# PreDAQ_Filter.net
KiCad netlist of a schematic drawn in Altium Designer
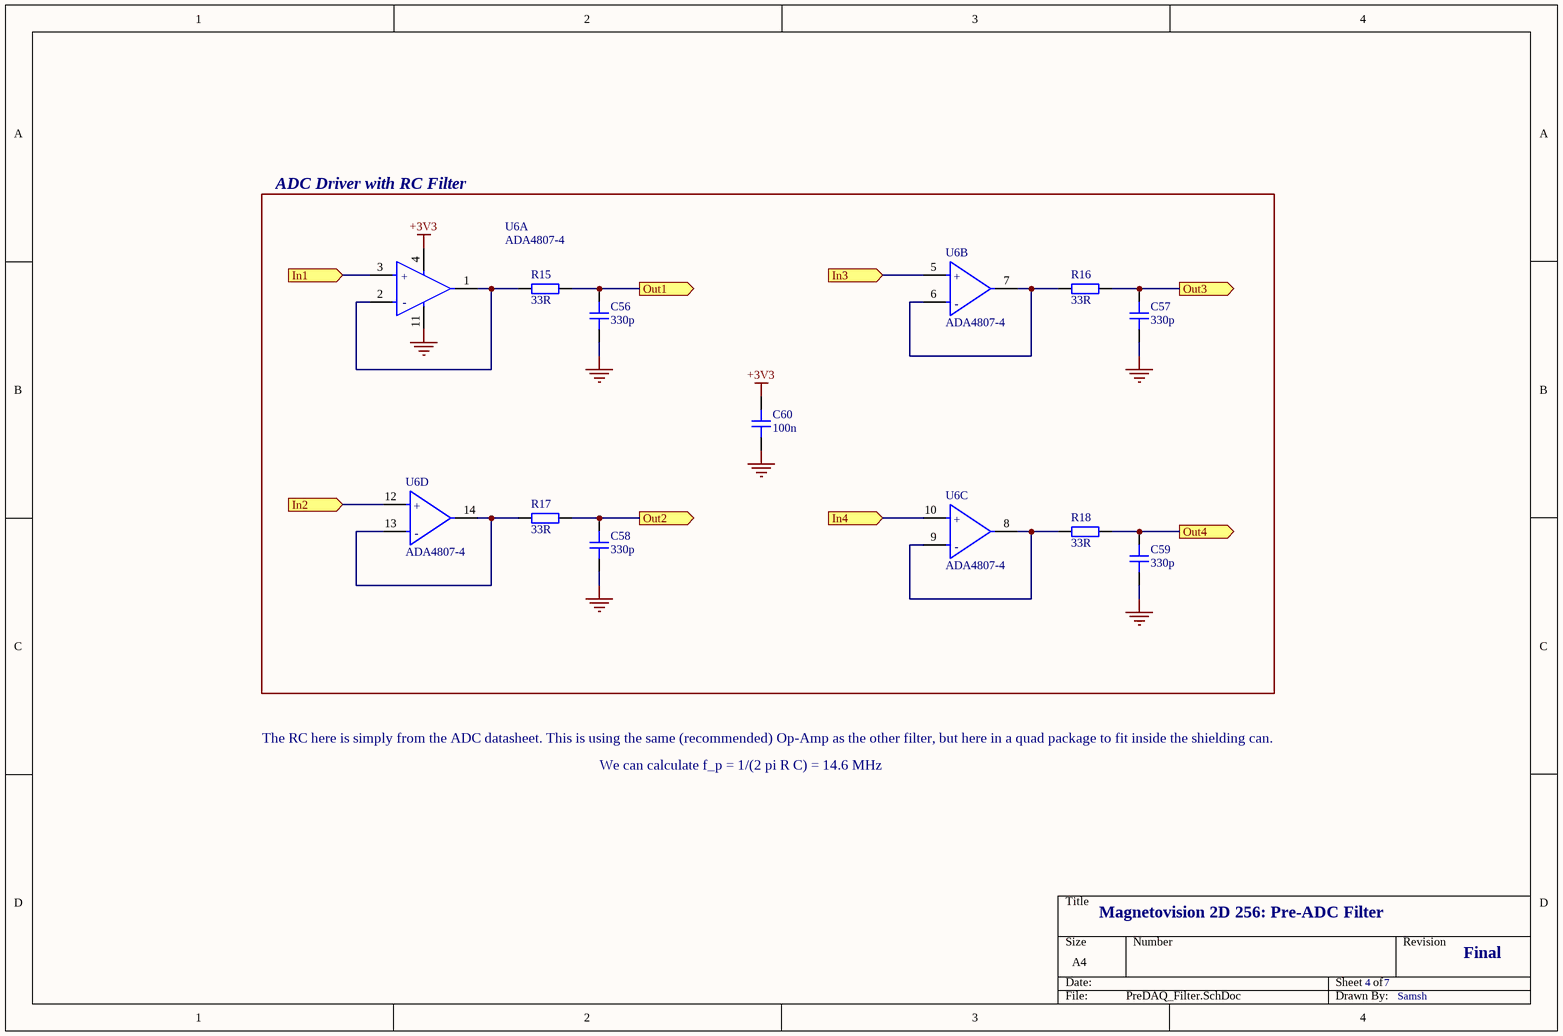
[diagram p0: PreDAQ_Filter.SchDoc]

(export (version "E")
  (design (tool "Eeschema 10.0.6"))
  (components
    (comp (ref "C56")
      (value "330p")
      (footprint "CAP_0603")
      (description "Capacitor SMD 0603")
      (fields (field (name "SOURCE") "Schematic-Lib-PhilsLab.SchLib"))
      (libsource (lib "Samsh Nanoelectronics") (part "CAP_EL_NP_5MM"))
    )
    (comp (ref "C57")
      (value "330p")
      (footprint "CAP_0603")
      (description "Capacitor SMD 0603")
      (fields (field (name "SOURCE") "Schematic-Lib-PhilsLab.SchLib"))
      (libsource (lib "Samsh Nanoelectronics") (part "CAP_EL_NP_5MM"))
    )
    (comp (ref "C58")
      (value "330p")
      (footprint "CAP_0603")
      (description "Capacitor SMD 0603")
      (fields (field (name "SOURCE") "Schematic-Lib-PhilsLab.SchLib"))
      (libsource (lib "Samsh Nanoelectronics") (part "CAP_EL_NP_5MM"))
    )
    (comp (ref "C59")
      (value "330p")
      (footprint "CAP_0603")
      (description "Capacitor SMD 0603")
      (fields (field (name "SOURCE") "Schematic-Lib-PhilsLab.SchLib"))
      (libsource (lib "Samsh Nanoelectronics") (part "CAP_EL_NP_5MM"))
    )
    (comp (ref "C60")
      (value "100n")
      (footprint "CAP_0603")
      (description "Capacitor SMD 0603")
      (fields (field (name "SOURCE") "Schematic-Lib-PhilsLab.SchLib"))
      (libsource (lib "Samsh Nanoelectronics") (part "CAP_EL_NP_5MM"))
    )
    (comp (ref "R15")
      (value "33R")
      (footprint "RES_0603")
      (description "Resistor SMD 0603")
      (fields (field (name "SOURCE") "Schematic-Lib-PhilsLab.SchLib"))
      (libsource (lib "Samsh Nanoelectronics") (part "RES_5931"))
    )
    (comp (ref "R16")
      (value "33R")
      (footprint "RES_0603")
      (description "Resistor SMD 0603")
      (fields (field (name "SOURCE") "Schematic-Lib-PhilsLab.SchLib"))
      (libsource (lib "Samsh Nanoelectronics") (part "RES_5931"))
    )
    (comp (ref "R17")
      (value "33R")
      (footprint "RES_0603")
      (description "Resistor SMD 0603")
      (fields (field (name "SOURCE") "Schematic-Lib-PhilsLab.SchLib"))
      (libsource (lib "Samsh Nanoelectronics") (part "RES_5931"))
    )
    (comp (ref "R18")
      (value "33R")
      (footprint "RES_0603")
      (description "Resistor SMD 0603")
      (fields (field (name "SOURCE") "Schematic-Lib-PhilsLab.SchLib"))
      (libsource (lib "Samsh Nanoelectronics") (part "RES_5931"))
    )
    (comp (ref "U6")
      (value "ADA4807-4")
      (footprint "FP-RU-14-IPC_A")
      (description "IC OPAMP VFB 4 CIRCUIT 14TSSOP")
      (libsource (lib "Altium Content Vault") (part "ef7bf8342113c21a595920e7812d995"))
    )
  )
  (nets
    (net (code "1") (name "+3V3") (class "Default")
      (node (ref "C60") (pin "2") (pinfunction "2_2") (pintype "passive"))
      (node (ref "U6") (pin "4") (pinfunction "+VS_4") (pintype "power_in"))
    )
    (net (code "2") (name "/In1") (class "Default")
      (node (ref "U6") (pin "3") (pinfunction "+IN1_3") (pintype "tri_state"))
    )
    (net (code "3") (name "/In2") (class "Default")
      (node (ref "U6") (pin "12") (pinfunction "+IN4_12") (pintype "tri_state"))
    )
    (net (code "4") (name "/In3") (class "Default")
      (node (ref "U6") (pin "5") (pinfunction "+IN2_5") (pintype "tri_state"))
    )
    (net (code "5") (name "/In4") (class "Default")
      (node (ref "U6") (pin "10") (pinfunction "+IN3_10") (pintype "tri_state"))
    )
    (net (code "6") (name "/Out1") (class "Default")
      (node (ref "C56") (pin "2") (pinfunction "2_2") (pintype "passive"))
      (node (ref "R15") (pin "1") (pinfunction "1_1") (pintype "passive"))
    )
    (net (code "7") (name "/Out2") (class "Default")
      (node (ref "C58") (pin "2") (pinfunction "2_2") (pintype "passive"))
      (node (ref "R17") (pin "1") (pinfunction "1_1") (pintype "passive"))
    )
    (net (code "8") (name "/Out3") (class "Default")
      (node (ref "C57") (pin "2") (pinfunction "2_2") (pintype "passive"))
      (node (ref "R16") (pin "1") (pinfunction "1_1") (pintype "passive"))
    )
    (net (code "9") (name "/Out4") (class "Default")
      (node (ref "C59") (pin "2") (pinfunction "2_2") (pintype "passive"))
      (node (ref "R18") (pin "1") (pinfunction "1_1") (pintype "passive"))
    )
    (net (code "10") (name "GND") (class "Default")
      (node (ref "C56") (pin "1") (pinfunction "1_1") (pintype "passive"))
      (node (ref "C57") (pin "1") (pinfunction "1_1") (pintype "passive"))
      (node (ref "C58") (pin "1") (pinfunction "1_1") (pintype "passive"))
      (node (ref "C59") (pin "1") (pinfunction "1_1") (pintype "passive"))
      (node (ref "C60") (pin "1") (pinfunction "1_1") (pintype "passive"))
      (node (ref "U6") (pin "11") (pinfunction "-VS_11") (pintype "power_in"))
    )
    (net (code "11") (name "Net-(U6A--IN1)") (class "Default")
      (node (ref "R15") (pin "2") (pinfunction "2_2") (pintype "passive"))
      (node (ref "U6") (pin "1") (pinfunction "VOUT1_1") (pintype "passive"))
      (node (ref "U6") (pin "2") (pinfunction "-IN1_2") (pintype "tri_state"))
    )
    (net (code "12") (name "Net-(U6B--IN2)") (class "Default")
      (node (ref "R16") (pin "2") (pinfunction "2_2") (pintype "passive"))
      (node (ref "U6") (pin "6") (pinfunction "-IN2_6") (pintype "tri_state"))
      (node (ref "U6") (pin "7") (pinfunction "VOUT2_7") (pintype "passive"))
    )
    (net (code "13") (name "Net-(U6C--IN3)") (class "Default")
      (node (ref "R18") (pin "2") (pinfunction "2_2") (pintype "passive"))
      (node (ref "U6") (pin "8") (pinfunction "VOUT3_8") (pintype "passive"))
      (node (ref "U6") (pin "9") (pinfunction "-IN3_9") (pintype "tri_state"))
    )
    (net (code "14") (name "Net-(U6D--IN4)") (class "Default")
      (node (ref "R17") (pin "2") (pinfunction "2_2") (pintype "passive"))
      (node (ref "U6") (pin "13") (pinfunction "-IN4_13") (pintype "tri_state"))
      (node (ref "U6") (pin "14") (pinfunction "VOUT4_14") (pintype "passive"))
    )
  )
)
